# MODUL_LAN_V102.net
KiCad netlist of a schematic drawn in EAGLE
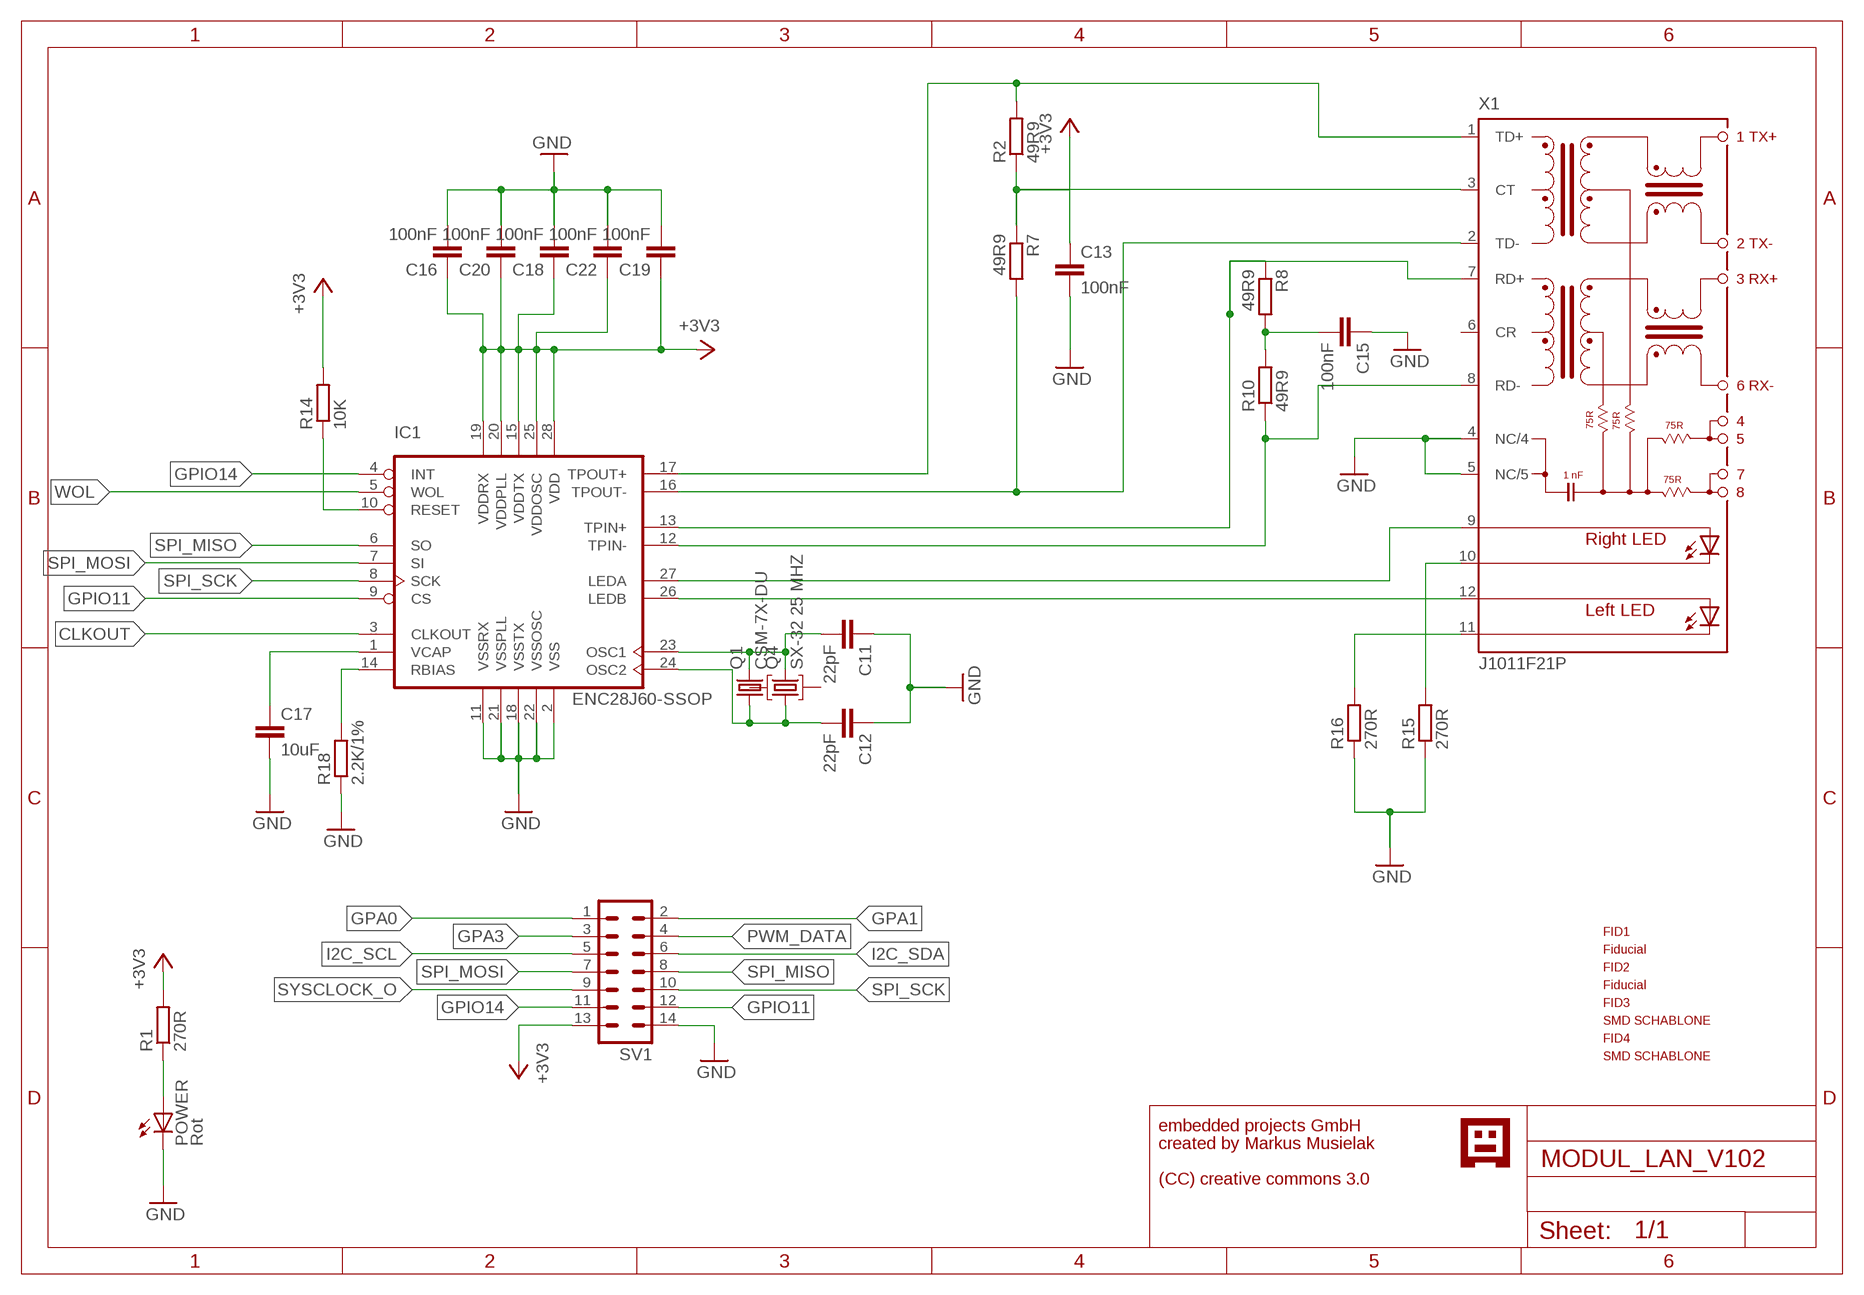
[diagram p0: schematic, sheet 1]

(export (version "E")
  (design (tool "Eeschema 10.0.6"))
  (components
    (comp (ref "C11")
      (value "22pF")
      (footprint "eagle-import:C0805")
      (libsource (lib "eagle-import") (part "C-EUC0805"))
    )
    (comp (ref "C12")
      (value "22pF")
      (footprint "eagle-import:C0805")
      (libsource (lib "eagle-import") (part "C-EUC0805"))
    )
    (comp (ref "C13")
      (value "100nF")
      (footprint "eagle-import:C0805")
      (libsource (lib "eagle-import") (part "C-EUC0805"))
    )
    (comp (ref "C15")
      (value "100nF")
      (footprint "eagle-import:C0805")
      (libsource (lib "eagle-import") (part "C-EUC0805"))
    )
    (comp (ref "C16")
      (value "100nF")
      (footprint "eagle-import:C0805")
      (libsource (lib "eagle-import") (part "C-EUC0805"))
    )
    (comp (ref "C17")
      (value "10uF")
      (footprint "eagle-import:C0805")
      (libsource (lib "eagle-import") (part "C-EUC0805"))
    )
    (comp (ref "C18")
      (value "100nF")
      (footprint "eagle-import:C0805")
      (libsource (lib "eagle-import") (part "C-EUC0805"))
    )
    (comp (ref "C19")
      (value "100nF")
      (footprint "eagle-import:C0805")
      (libsource (lib "eagle-import") (part "C-EUC0805"))
    )
    (comp (ref "C20")
      (value "100nF")
      (footprint "eagle-import:C0805")
      (libsource (lib "eagle-import") (part "C-EUC0805"))
    )
    (comp (ref "C22")
      (value "100nF")
      (footprint "eagle-import:C0805")
      (libsource (lib "eagle-import") (part "C-EUC0805"))
    )
    (comp (ref "FID1")
      (value "PASSERMARKEN_FIDUCIAL")
      (footprint "eagle-import:PASSERMARKEN_FIDUCIAL")
      (libsource (lib "eagle-import") (part "PASSERMARKEN_FIDUCIAL"))
    )
    (comp (ref "FID2")
      (value "PASSERMARKEN_FIDUCIAL")
      (footprint "eagle-import:PASSERMARKEN_FIDUCIAL")
      (libsource (lib "eagle-import") (part "PASSERMARKEN_FIDUCIAL"))
    )
    (comp (ref "FID3")
      (value "PASSERMARKEN_FIDUCIAL")
      (footprint "eagle-import:PASSERMARKEN_FIDUCIAL")
      (libsource (lib "eagle-import") (part "SMDSCHABLONE_PASSERMARKEN_FIDUCIAL"))
    )
    (comp (ref "FID4")
      (value "PASSERMARKEN_FIDUCIAL")
      (footprint "eagle-import:PASSERMARKEN_FIDUCIAL")
      (libsource (lib "eagle-import") (part "SMDSCHABLONE_PASSERMARKEN_FIDUCIAL"))
    )
    (comp (ref "IC1")
      (value "ENC28J60-SSOP")
      (footprint "eagle-import:SSOP28")
      (libsource (lib "eagle-import") (part "ENC28J60-SSOP"))
    )
    (comp (ref "POWER")
      (value "Rot")
      (footprint "eagle-import:CHIP-LED0805")
      (libsource (lib "eagle-import") (part "LEDCHIP-LED0805"))
    )
    (comp (ref "Q1")
      (value "CSM-7X-DU")
      (footprint "eagle-import:CSM-7X-DU")
      (libsource (lib "eagle-import") (part "CSM-7X-DU"))
    )
    (comp (ref "Q4")
      (value "SX-32 25 MHZ")
      (footprint "eagle-import:SX-32")
      (libsource (lib "eagle-import") (part "SX-32"))
    )
    (comp (ref "R1")
      (value "270R")
      (footprint "eagle-import:R0805")
      (libsource (lib "eagle-import") (part "R-EU_R0805"))
    )
    (comp (ref "R2")
      (value "49R9")
      (footprint "eagle-import:R0805")
      (libsource (lib "eagle-import") (part "R-EU_R0805"))
    )
    (comp (ref "R7")
      (value "49R9")
      (footprint "eagle-import:R0805")
      (libsource (lib "eagle-import") (part "R-EU_R0805"))
    )
    (comp (ref "R8")
      (value "49R9")
      (footprint "eagle-import:R0805")
      (libsource (lib "eagle-import") (part "R-EU_R0805"))
    )
    (comp (ref "R10")
      (value "49R9")
      (footprint "eagle-import:R0805")
      (libsource (lib "eagle-import") (part "R-EU_R0805"))
    )
    (comp (ref "R14")
      (value "10K")
      (footprint "eagle-import:R0805")
      (libsource (lib "eagle-import") (part "R-EU_R0805"))
    )
    (comp (ref "R15")
      (value "270R")
      (footprint "eagle-import:R0805")
      (libsource (lib "eagle-import") (part "R-EU_R0805"))
    )
    (comp (ref "R16")
      (value "270R")
      (footprint "eagle-import:R0805")
      (libsource (lib "eagle-import") (part "R-EU_R0805"))
    )
    (comp (ref "R18")
      (value "2.2K/1%")
      (footprint "eagle-import:R0805")
      (libsource (lib "eagle-import") (part "R-EU_R0805"))
    )
    (comp (ref "SV1")
      (value "ML14")
      (footprint "eagle-import:ML14")
      (libsource (lib "eagle-import") (part "ML14"))
    )
    (comp (ref "U$2")
      (value "GNUBLINLOGOSIEB")
      (footprint "eagle-import:GNUSIEBDRUCK")
      (libsource (lib "eagle-import") (part "GNUBLINLOGOSIEB"))
    )
    (comp (ref "X1")
      (value "J1011F21P")
      (footprint "eagle-import:J1")
      (libsource (lib "eagle-import") (part "J1011F21P"))
    )
  )
  (nets
    (net (code "1") (name "+3V3") (class "Default")
      (node (ref "C13") (pin "1") (pinfunction "1_1") (pintype "passive"))
      (node (ref "C16") (pin "1") (pinfunction "1_1") (pintype "passive"))
      (node (ref "C18") (pin "1") (pinfunction "1_1") (pintype "passive"))
      (node (ref "C19") (pin "1") (pinfunction "1_1") (pintype "passive"))
      (node (ref "C20") (pin "1") (pinfunction "1_1") (pintype "passive"))
      (node (ref "C22") (pin "1") (pinfunction "1_1") (pintype "passive"))
      (node (ref "IC1") (pin "15") (pinfunction "VDDTX_15") (pintype "power_in"))
      (node (ref "IC1") (pin "19") (pinfunction "VDDRX_19") (pintype "power_in"))
      (node (ref "IC1") (pin "20") (pinfunction "VDDPLL_20") (pintype "power_in"))
      (node (ref "IC1") (pin "25") (pinfunction "VDDOSC_25") (pintype "power_in"))
      (node (ref "IC1") (pin "28") (pinfunction "VDD_28") (pintype "power_in"))
      (node (ref "R1") (pin "2") (pinfunction "2_2") (pintype "passive"))
      (node (ref "R14") (pin "2") (pinfunction "2_2") (pintype "passive"))
      (node (ref "R2") (pin "1") (pinfunction "1_1") (pintype "passive"))
      (node (ref "R7") (pin "1") (pinfunction "1_1") (pintype "passive"))
      (node (ref "SV1") (pin "13") (pinfunction "13_13") (pintype "passive"))
      (node (ref "X1") (pin "3") (pinfunction "CT_3") (pintype "input"))
    )
    (net (code "2") (name "CLKOUT") (class "Default")
      (node (ref "IC1") (pin "3") (pinfunction "CLKOUT_3") (pintype "output"))
    )
    (net (code "3") (name "GND") (class "Default")
      (node (ref "C11") (pin "1") (pinfunction "1_1") (pintype "passive"))
      (node (ref "C12") (pin "1") (pinfunction "1_1") (pintype "passive"))
      (node (ref "C13") (pin "2") (pinfunction "2_2") (pintype "passive"))
      (node (ref "C15") (pin "1") (pinfunction "1_1") (pintype "passive"))
      (node (ref "C16") (pin "2") (pinfunction "2_2") (pintype "passive"))
      (node (ref "C17") (pin "2") (pinfunction "2_2") (pintype "passive"))
      (node (ref "C18") (pin "2") (pinfunction "2_2") (pintype "passive"))
      (node (ref "C19") (pin "2") (pinfunction "2_2") (pintype "passive"))
      (node (ref "C20") (pin "2") (pinfunction "2_2") (pintype "passive"))
      (node (ref "C22") (pin "2") (pinfunction "2_2") (pintype "passive"))
      (node (ref "IC1") (pin "11") (pinfunction "VSSRX_11") (pintype "power_in"))
      (node (ref "IC1") (pin "18") (pinfunction "VSSTX_18") (pintype "power_in"))
      (node (ref "IC1") (pin "2") (pinfunction "VSS_2") (pintype "power_in"))
      (node (ref "IC1") (pin "21") (pinfunction "VSSPLL_21") (pintype "power_in"))
      (node (ref "IC1") (pin "22") (pinfunction "VSSOSC_22") (pintype "power_in"))
      (node (ref "POWER") (pin "C") (pinfunction "C_C") (pintype "passive"))
      (node (ref "R15") (pin "1") (pinfunction "1_1") (pintype "passive"))
      (node (ref "R16") (pin "1") (pinfunction "1_1") (pintype "passive"))
      (node (ref "R18") (pin "1") (pinfunction "1_1") (pintype "passive"))
      (node (ref "SV1") (pin "14") (pinfunction "14_14") (pintype "passive"))
      (node (ref "X1") (pin "4") (pinfunction "NC/4_4") (pintype "input"))
      (node (ref "X1") (pin "5") (pinfunction "NC/5_5") (pintype "input"))
    )
    (net (code "4") (name "GPA0") (class "Default")
      (node (ref "SV1") (pin "1") (pinfunction "1_1") (pintype "passive"))
    )
    (net (code "5") (name "GPA1") (class "Default")
      (node (ref "SV1") (pin "2") (pinfunction "2_2") (pintype "passive"))
    )
    (net (code "6") (name "GPA3") (class "Default")
      (node (ref "SV1") (pin "3") (pinfunction "3_3") (pintype "passive"))
    )
    (net (code "7") (name "GPIO11") (class "Default")
      (node (ref "IC1") (pin "9") (pinfunction "CS_9") (pintype "input"))
      (node (ref "SV1") (pin "12") (pinfunction "12_12") (pintype "passive"))
    )
    (net (code "8") (name "GPIO14") (class "Default")
      (node (ref "IC1") (pin "4") (pinfunction "INT_4") (pintype "output"))
      (node (ref "SV1") (pin "11") (pinfunction "11_11") (pintype "passive"))
    )
    (net (code "9") (name "I2C_SCL") (class "Default")
      (node (ref "SV1") (pin "5") (pinfunction "5_5") (pintype "passive"))
    )
    (net (code "10") (name "I2C_SDA") (class "Default")
      (node (ref "SV1") (pin "6") (pinfunction "6_6") (pintype "passive"))
    )
    (net (code "11") (name "Net-(C15-Pad2)") (class "Default")
      (node (ref "C15") (pin "2") (pinfunction "2_2") (pintype "passive"))
      (node (ref "R10") (pin "2") (pinfunction "2_2") (pintype "passive"))
      (node (ref "R8") (pin "2") (pinfunction "2_2") (pintype "passive"))
    )
    (net (code "12") (name "Net-(IC1-LEDA)") (class "Default")
      (node (ref "IC1") (pin "27") (pinfunction "LEDA_27") (pintype "output"))
      (node (ref "X1") (pin "9") (pinfunction "A-R_9") (pintype "passive"))
    )
    (net (code "13") (name "Net-(IC1-LEDB)") (class "Default")
      (node (ref "IC1") (pin "26") (pinfunction "LEDB_26") (pintype "output"))
      (node (ref "X1") (pin "12") (pinfunction "AL_12") (pintype "passive"))
    )
    (net (code "14") (name "Net-(IC1-OSC1)") (class "Default")
      (node (ref "C11") (pin "2") (pinfunction "2_2") (pintype "passive"))
      (node (ref "IC1") (pin "23") (pinfunction "OSC1_23") (pintype "input"))
      (node (ref "Q1") (pin "2") (pinfunction "2_2") (pintype "passive"))
      (node (ref "Q4") (pin "3") (pinfunction "2_3") (pintype "passive"))
    )
    (net (code "15") (name "Net-(IC1-OSC2)") (class "Default")
      (node (ref "C12") (pin "2") (pinfunction "2_2") (pintype "passive"))
      (node (ref "IC1") (pin "24") (pinfunction "OSC2_24") (pintype "output"))
      (node (ref "Q1") (pin "1") (pinfunction "1_1") (pintype "passive"))
      (node (ref "Q4") (pin "1") (pinfunction "1_1") (pintype "passive"))
    )
    (net (code "16") (name "Net-(IC1-RBIAS)") (class "Default")
      (node (ref "IC1") (pin "14") (pinfunction "RBIAS_14") (pintype "passive"))
      (node (ref "R18") (pin "2") (pinfunction "2_2") (pintype "passive"))
    )
    (net (code "17") (name "Net-(IC1-RESET)") (class "Default")
      (node (ref "IC1") (pin "10") (pinfunction "RESET_10") (pintype "input"))
      (node (ref "R14") (pin "1") (pinfunction "1_1") (pintype "passive"))
    )
    (net (code "18") (name "Net-(IC1-TPIN+)") (class "Default")
      (node (ref "IC1") (pin "13") (pinfunction "TPIN+_13") (pintype "input"))
      (node (ref "R8") (pin "1") (pinfunction "1_1") (pintype "passive"))
      (node (ref "X1") (pin "7") (pinfunction "RD+_7") (pintype "input"))
    )
    (net (code "19") (name "Net-(IC1-TPIN-)") (class "Default")
      (node (ref "IC1") (pin "12") (pinfunction "TPIN-_12") (pintype "input"))
      (node (ref "R10") (pin "1") (pinfunction "1_1") (pintype "passive"))
      (node (ref "X1") (pin "8") (pinfunction "RD-_8") (pintype "input"))
    )
    (net (code "20") (name "Net-(IC1-TPOUT+)") (class "Default")
      (node (ref "IC1") (pin "17") (pinfunction "TPOUT+_17") (pintype "output"))
      (node (ref "R2") (pin "2") (pinfunction "2_2") (pintype "passive"))
      (node (ref "X1") (pin "1") (pinfunction "TD+_1") (pintype "input"))
    )
    (net (code "21") (name "Net-(IC1-TPOUT-)") (class "Default")
      (node (ref "IC1") (pin "16") (pinfunction "TPOUT-_16") (pintype "output"))
      (node (ref "R7") (pin "2") (pinfunction "2_2") (pintype "passive"))
      (node (ref "X1") (pin "2") (pinfunction "TD-_2") (pintype "input"))
    )
    (net (code "22") (name "Net-(IC1-VCAP)") (class "Default")
      (node (ref "C17") (pin "1") (pinfunction "1_1") (pintype "passive"))
      (node (ref "IC1") (pin "1") (pinfunction "VCAP_1") (pintype "power_in"))
    )
    (net (code "23") (name "Net-(POWER-PadA)") (class "Default")
      (node (ref "POWER") (pin "A") (pinfunction "A_A") (pintype "passive"))
      (node (ref "R1") (pin "1") (pinfunction "1_1") (pintype "passive"))
    )
    (net (code "24") (name "Net-(X1-C-L)") (class "Default")
      (node (ref "R16") (pin "2") (pinfunction "2_2") (pintype "passive"))
      (node (ref "X1") (pin "11") (pinfunction "C-L_11") (pintype "passive"))
    )
    (net (code "25") (name "Net-(X1-C-R)") (class "Default")
      (node (ref "R15") (pin "2") (pinfunction "2_2") (pintype "passive"))
      (node (ref "X1") (pin "10") (pinfunction "C-R_10") (pintype "passive"))
    )
    (net (code "26") (name "PWM_DATA") (class "Default")
      (node (ref "SV1") (pin "4") (pinfunction "4_4") (pintype "passive"))
    )
    (net (code "27") (name "SPI_MISO") (class "Default")
      (node (ref "IC1") (pin "6") (pinfunction "SO_6") (pintype "open_collector"))
      (node (ref "SV1") (pin "8") (pinfunction "8_8") (pintype "passive"))
    )
    (net (code "28") (name "SPI_MOSI") (class "Default")
      (node (ref "IC1") (pin "7") (pinfunction "SI_7") (pintype "input"))
      (node (ref "SV1") (pin "7") (pinfunction "7_7") (pintype "passive"))
    )
    (net (code "29") (name "SPI_SCK") (class "Default")
      (node (ref "IC1") (pin "8") (pinfunction "SCK_8") (pintype "input"))
      (node (ref "SV1") (pin "10") (pinfunction "10_10") (pintype "passive"))
    )
    (net (code "30") (name "SYSCLOCK_O") (class "Default")
      (node (ref "SV1") (pin "9") (pinfunction "9_9") (pintype "passive"))
    )
    (net (code "31") (name "WOL") (class "Default")
      (node (ref "IC1") (pin "5") (pinfunction "WOL_5") (pintype "output"))
    )
    (net (code "32") (name "unconnected-(Q4-3-Pad2)") (class "Default")
      (node (ref "Q4") (pin "2") (pinfunction "3_2") (pintype "passive"))
    )
    (net (code "33") (name "unconnected-(Q4-Pad4)") (class "Default")
      (node (ref "Q4") (pin "4") (pinfunction "4_4") (pintype "passive"))
    )
    (net (code "34") (name "unconnected-(X1-CR-Pad6)") (class "Default")
      (node (ref "X1") (pin "6") (pinfunction "CR_6") (pintype "input"))
    )
  )
)
